# StEth32_Base_XLR_Output.net
KiCad netlist of a schematic drawn in Altium Designer
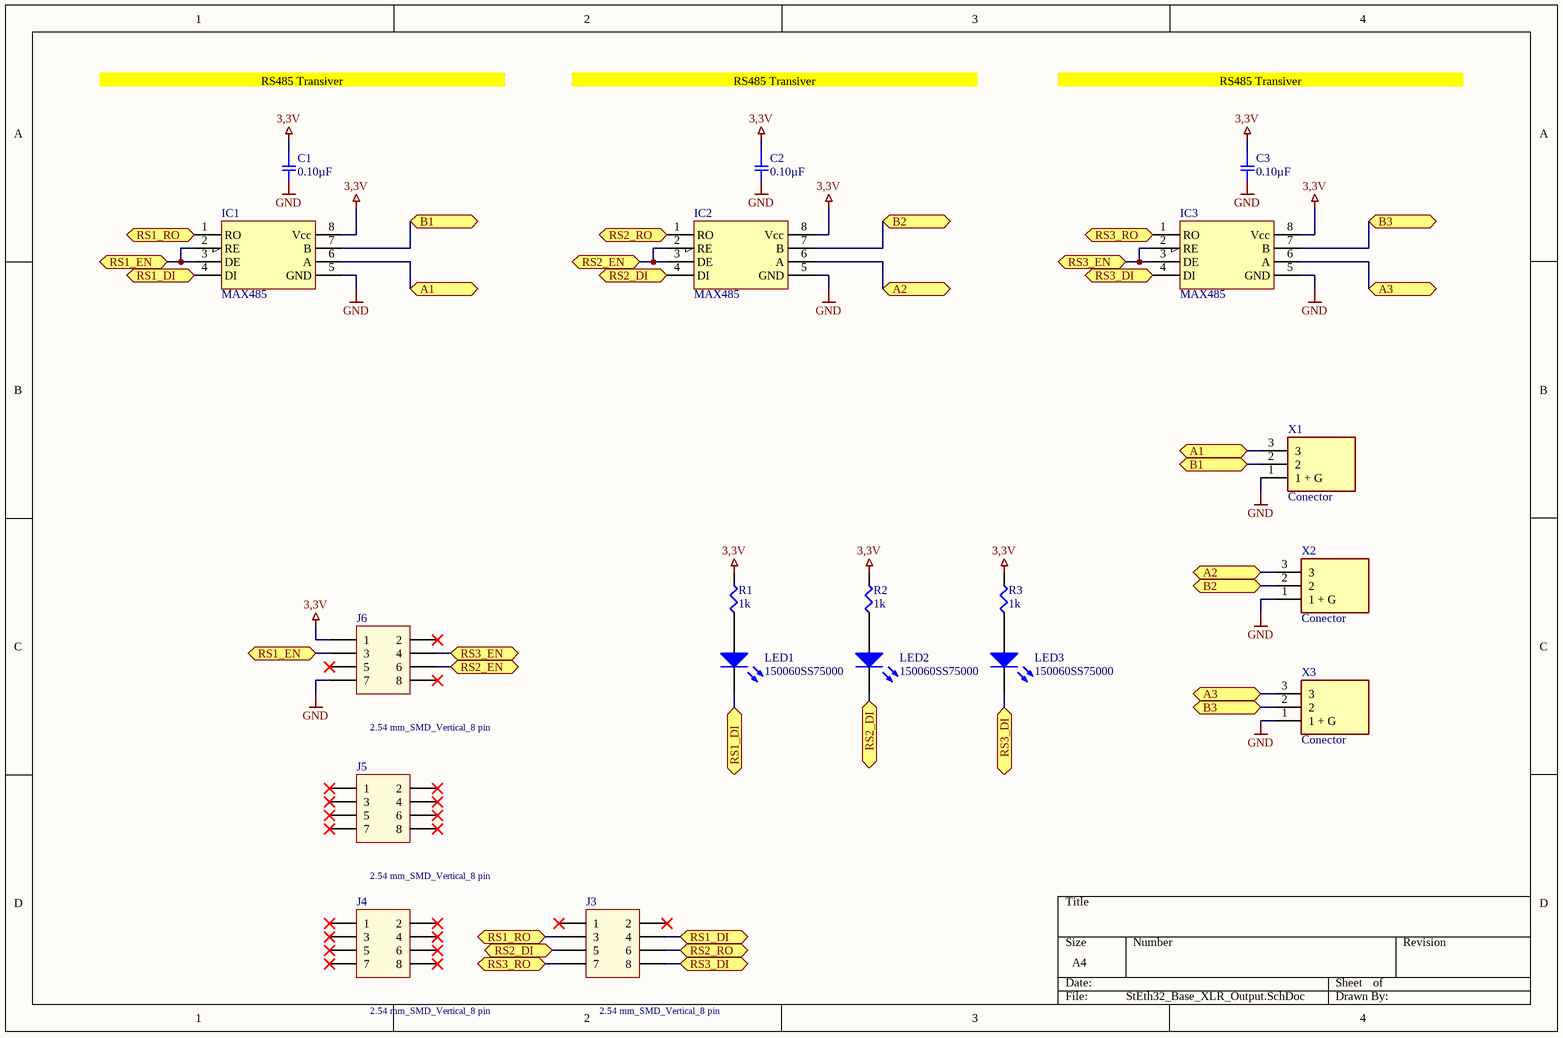
[diagram p0: StEth32_Base_XLR_Output.SchDoc]

(export (version "E")
  (design (tool "Eeschema 10.0.6"))
  (components
    (comp (ref "C1")
      (value "0.10µF")
      (footprint "SMD-0603C")
      (description "CAP CER 0.1UF 16V X7R 0603")
      (fields
        (field (name "DIGI-KEY PART NUMBER") "490-8015-1-ND")
        (field (name "PART NUMBER") "GCM188R71C104KA37J")
      )
      (libsource (lib "capacitor_murata_0603") (part "GCM188R71C104KA37J"))
    )
    (comp (ref "C2")
      (value "0.10µF")
      (footprint "SMD-0603C")
      (description "CAP CER 0.1UF 16V X7R 0603")
      (fields
        (field (name "DIGI-KEY PART NUMBER") "490-8015-1-ND")
        (field (name "PART NUMBER") "GCM188R71C104KA37J")
      )
      (libsource (lib "capacitor_murata_0603") (part "GCM188R71C104KA37J"))
    )
    (comp (ref "C3")
      (value "0.10µF")
      (footprint "SMD-0603C")
      (description "CAP CER 0.1UF 16V X7R 0603")
      (fields
        (field (name "DIGI-KEY PART NUMBER") "490-8015-1-ND")
        (field (name "PART NUMBER") "GCM188R71C104KA37J")
      )
      (libsource (lib "capacitor_murata_0603") (part "GCM188R71C104KA37J"))
    )
    (comp (ref "IC1") (value "MAX485") (footprint "D008_L") (libsource (lib "MyLibs") (part "MAX485")))
    (comp (ref "IC2") (value "MAX485") (footprint "D008_L") (libsource (lib "MyLibs") (part "MAX485")))
    (comp (ref "IC3") (value "MAX485") (footprint "D008_L") (libsource (lib "MyLibs") (part "MAX485")))
    (comp (ref "J3")
      (value "2.54 mm_SMD_Vertical_8 pin")
      (footprint "61030821121")
      (description "Pin Header WR-PHD, pitch 2.54 mm, SMD, Vertical, dual row, 8 pin")
      (fields (field (name "PART NUMBER") "61030821121") (field (name "PUBLISHER") "Wurth Elektronik"))
      (libsource (lib "Altium_WR-PHD_PIN_HEADER_2_54 (rev18a)") (part "61030821121"))
    )
    (comp (ref "J4")
      (value "2.54 mm_SMD_Vertical_8 pin")
      (footprint "61030821121")
      (description "Pin Header WR-PHD, pitch 2.54 mm, SMD, Vertical, dual row, 8 pin")
      (fields (field (name "PART NUMBER") "61030821121") (field (name "PUBLISHER") "Wurth Elektronik"))
      (libsource (lib "Altium_WR-PHD_PIN_HEADER_2_54 (rev18a)") (part "61030821121"))
    )
    (comp (ref "J5")
      (value "2.54 mm_SMD_Vertical_8 pin")
      (footprint "61030821121")
      (description "Pin Header WR-PHD, pitch 2.54 mm, SMD, Vertical, dual row, 8 pin")
      (fields (field (name "PART NUMBER") "61030821121") (field (name "PUBLISHER") "Wurth Elektronik"))
      (libsource (lib "Altium_WR-PHD_PIN_HEADER_2_54 (rev18a)") (part "61030821121"))
    )
    (comp (ref "J6")
      (value "2.54 mm_SMD_Vertical_8 pin")
      (footprint "61030821121")
      (description "Pin Header WR-PHD, pitch 2.54 mm, SMD, Vertical, dual row, 8 pin")
      (fields (field (name "PART NUMBER") "61030821121") (field (name "PUBLISHER") "Wurth Elektronik"))
      (libsource (lib "Altium_WR-PHD_PIN_HEADER_2_54 (rev18a)") (part "61030821121"))
    )
    (comp (ref "LED1")
      (value "150060SS75000")
      (footprint "0603_A")
      (description "SMD mono-color Chip LED, WL-SMCW, Super Red")
      (libsource (lib "WL-SMCW SMD chip LED top view mono-color waterclear") (part "150060SS75000"))
    )
    (comp (ref "LED2")
      (value "150060SS75000")
      (footprint "0603_A")
      (description "SMD mono-color Chip LED, WL-SMCW, Super Red")
      (libsource (lib "WL-SMCW SMD chip LED top view mono-color waterclear") (part "150060SS75000"))
    )
    (comp (ref "LED3")
      (value "150060SS75000")
      (footprint "0603_A")
      (description "SMD mono-color Chip LED, WL-SMCW, Super Red")
      (libsource (lib "WL-SMCW SMD chip LED top view mono-color waterclear") (part "150060SS75000"))
    )
    (comp (ref "R1")
      (value "1k")
      (footprint "SMD-0603-RES")
      (description "RES SMD 1K OHM 1% 1/4W 0603")
      (fields
        (field (name "PART NUMBER") "ERJ-PA3F1001V")
        (field (name "DIGI-KEY PART NUMBER") "P1.0KBYCT-ND")
      )
      (libsource (lib "Panasonic_ERJ_0603") (part "ERJ-PA3F1001V"))
    )
    (comp (ref "R2")
      (value "1k")
      (footprint "SMD-0603-RES")
      (description "RES SMD 1K OHM 1% 1/4W 0603")
      (fields
        (field (name "PART NUMBER") "ERJ-PA3F1001V")
        (field (name "DIGI-KEY PART NUMBER") "P1.0KBYCT-ND")
      )
      (libsource (lib "Panasonic_ERJ_0603") (part "ERJ-PA3F1001V"))
    )
    (comp (ref "R3")
      (value "1k")
      (footprint "SMD-0603-RES")
      (description "RES SMD 1K OHM 1% 1/4W 0603")
      (fields
        (field (name "PART NUMBER") "ERJ-PA3F1001V")
        (field (name "DIGI-KEY PART NUMBER") "P1.0KBYCT-ND")
      )
      (libsource (lib "Panasonic_ERJ_0603") (part "ERJ-PA3F1001V"))
    )
    (comp (ref "X1")
      (value "Conector")
      (footprint "NC3FAAV1")
      (description "Neutrik XLR Connector")
      (libsource (lib "MyLibs") (part "NC3FAAV1"))
    )
    (comp (ref "X2")
      (value "Conector")
      (footprint "NC3FAAV1")
      (description "Neutrik XLR Connector")
      (libsource (lib "MyLibs") (part "NC3FAAV1"))
    )
    (comp (ref "X3")
      (value "Conector")
      (footprint "NC3FAAV1")
      (description "Neutrik XLR Connector")
      (libsource (lib "MyLibs") (part "NC3FAAV1"))
    )
  )
  (nets
    (net (code "1") (name "/A1") (class "Default")
      (node (ref "IC1") (pin "6") (pinfunction "A_6") (pintype "passive"))
      (node (ref "X1") (pin "3") (pinfunction "3_3") (pintype "passive"))
    )
    (net (code "2") (name "/A2") (class "Default")
      (node (ref "IC2") (pin "6") (pinfunction "A_6") (pintype "passive"))
      (node (ref "X2") (pin "3") (pinfunction "3_3") (pintype "passive"))
    )
    (net (code "3") (name "/A3") (class "Default")
      (node (ref "IC3") (pin "6") (pinfunction "A_6") (pintype "passive"))
      (node (ref "X3") (pin "3") (pinfunction "3_3") (pintype "passive"))
    )
    (net (code "4") (name "/B1") (class "Default")
      (node (ref "IC1") (pin "7") (pinfunction "B_7") (pintype "passive"))
      (node (ref "X1") (pin "2") (pinfunction "2_2") (pintype "passive"))
    )
    (net (code "5") (name "/B2") (class "Default")
      (node (ref "IC2") (pin "7") (pinfunction "B_7") (pintype "passive"))
      (node (ref "X2") (pin "2") (pinfunction "2_2") (pintype "passive"))
    )
    (net (code "6") (name "/B3") (class "Default")
      (node (ref "IC3") (pin "7") (pinfunction "B_7") (pintype "passive"))
      (node (ref "X3") (pin "2") (pinfunction "2_2") (pintype "passive"))
    )
    (net (code "7") (name "/RS1_DI") (class "Default")
      (node (ref "IC1") (pin "4") (pinfunction "DI_4") (pintype "passive"))
      (node (ref "J3") (pin "4") (pinfunction "4_4") (pintype "passive"))
      (node (ref "LED1") (pin "1") (pinfunction "K_1") (pintype "passive"))
    )
    (net (code "8") (name "/RS1_EN") (class "Default")
      (node (ref "IC1") (pin "2") (pinfunction "RE_2") (pintype "passive"))
      (node (ref "IC1") (pin "3") (pinfunction "DE_3") (pintype "passive"))
      (node (ref "J6") (pin "3") (pinfunction "3_3") (pintype "passive"))
    )
    (net (code "9") (name "/RS1_RO") (class "Default")
      (node (ref "IC1") (pin "1") (pinfunction "RO_1") (pintype "passive"))
      (node (ref "J3") (pin "3") (pinfunction "3_3") (pintype "passive"))
    )
    (net (code "10") (name "/RS2_DI") (class "Default")
      (node (ref "IC2") (pin "4") (pinfunction "DI_4") (pintype "passive"))
      (node (ref "J3") (pin "5") (pinfunction "5_5") (pintype "passive"))
      (node (ref "LED2") (pin "1") (pinfunction "K_1") (pintype "passive"))
    )
    (net (code "11") (name "/RS2_EN") (class "Default")
      (node (ref "IC2") (pin "2") (pinfunction "RE_2") (pintype "passive"))
      (node (ref "IC2") (pin "3") (pinfunction "DE_3") (pintype "passive"))
      (node (ref "J6") (pin "6") (pinfunction "6_6") (pintype "passive"))
    )
    (net (code "12") (name "/RS2_RO") (class "Default")
      (node (ref "IC2") (pin "1") (pinfunction "RO_1") (pintype "passive"))
      (node (ref "J3") (pin "6") (pinfunction "6_6") (pintype "passive"))
    )
    (net (code "13") (name "/RS3_DI") (class "Default")
      (node (ref "IC3") (pin "4") (pinfunction "DI_4") (pintype "passive"))
      (node (ref "J3") (pin "8") (pinfunction "8_8") (pintype "passive"))
      (node (ref "LED3") (pin "1") (pinfunction "K_1") (pintype "passive"))
    )
    (net (code "14") (name "/RS3_EN") (class "Default")
      (node (ref "IC3") (pin "2") (pinfunction "RE_2") (pintype "passive"))
      (node (ref "IC3") (pin "3") (pinfunction "DE_3") (pintype "passive"))
      (node (ref "J6") (pin "4") (pinfunction "4_4") (pintype "passive"))
    )
    (net (code "15") (name "/RS3_RO") (class "Default")
      (node (ref "IC3") (pin "1") (pinfunction "RO_1") (pintype "passive"))
      (node (ref "J3") (pin "7") (pinfunction "7_7") (pintype "passive"))
    )
    (net (code "16") (name "3,3V") (class "Default")
      (node (ref "C1") (pin "1") (pinfunction "1_1") (pintype "passive"))
      (node (ref "C2") (pin "1") (pinfunction "1_1") (pintype "passive"))
      (node (ref "C3") (pin "1") (pinfunction "1_1") (pintype "passive"))
      (node (ref "IC1") (pin "8") (pinfunction "Vcc_8") (pintype "passive"))
      (node (ref "IC2") (pin "8") (pinfunction "Vcc_8") (pintype "passive"))
      (node (ref "IC3") (pin "8") (pinfunction "Vcc_8") (pintype "passive"))
      (node (ref "J6") (pin "1") (pinfunction "1_1") (pintype "passive"))
      (node (ref "R1") (pin "2") (pinfunction "2_2") (pintype "passive"))
      (node (ref "R2") (pin "2") (pinfunction "2_2") (pintype "passive"))
      (node (ref "R3") (pin "2") (pinfunction "2_2") (pintype "passive"))
    )
    (net (code "17") (name "GND") (class "Default")
      (node (ref "C1") (pin "2") (pinfunction "2_2") (pintype "passive"))
      (node (ref "C2") (pin "2") (pinfunction "2_2") (pintype "passive"))
      (node (ref "C3") (pin "2") (pinfunction "2_2") (pintype "passive"))
      (node (ref "IC1") (pin "5") (pinfunction "GND_5") (pintype "passive"))
      (node (ref "IC2") (pin "5") (pinfunction "GND_5") (pintype "passive"))
      (node (ref "IC3") (pin "5") (pinfunction "GND_5") (pintype "passive"))
      (node (ref "J6") (pin "7") (pinfunction "7_7") (pintype "passive"))
      (node (ref "X1") (pin "1") (pinfunction "1_+_G_1") (pintype "passive"))
      (node (ref "X2") (pin "1") (pinfunction "1_+_G_1") (pintype "passive"))
      (node (ref "X3") (pin "1") (pinfunction "1_+_G_1") (pintype "passive"))
    )
    (net (code "18") (name "Net-(LED1-A)") (class "Default")
      (node (ref "LED1") (pin "2") (pinfunction "A_2") (pintype "passive"))
      (node (ref "R1") (pin "1") (pinfunction "1_1") (pintype "passive"))
    )
    (net (code "19") (name "Net-(LED2-A)") (class "Default")
      (node (ref "LED2") (pin "2") (pinfunction "A_2") (pintype "passive"))
      (node (ref "R2") (pin "1") (pinfunction "1_1") (pintype "passive"))
    )
    (net (code "20") (name "Net-(LED3-A)") (class "Default")
      (node (ref "LED3") (pin "2") (pinfunction "A_2") (pintype "passive"))
      (node (ref "R3") (pin "1") (pinfunction "1_1") (pintype "passive"))
    )
    (net (code "21") (name "unconnected-(J3-Pad1)") (class "Default")
      (node (ref "J3") (pin "1") (pinfunction "1_1") (pintype "passive+no_connect"))
    )
    (net (code "22") (name "unconnected-(J3-Pad2)") (class "Default")
      (node (ref "J3") (pin "2") (pinfunction "2_2") (pintype "passive+no_connect"))
    )
    (net (code "23") (name "unconnected-(J4-Pad1)") (class "Default")
      (node (ref "J4") (pin "1") (pinfunction "1_1") (pintype "passive+no_connect"))
    )
    (net (code "24") (name "unconnected-(J4-Pad2)") (class "Default")
      (node (ref "J4") (pin "2") (pinfunction "2_2") (pintype "passive+no_connect"))
    )
    (net (code "25") (name "unconnected-(J4-Pad3)") (class "Default")
      (node (ref "J4") (pin "3") (pinfunction "3_3") (pintype "passive+no_connect"))
    )
    (net (code "26") (name "unconnected-(J4-Pad4)") (class "Default")
      (node (ref "J4") (pin "4") (pinfunction "4_4") (pintype "passive+no_connect"))
    )
    (net (code "27") (name "unconnected-(J4-Pad5)") (class "Default")
      (node (ref "J4") (pin "5") (pinfunction "5_5") (pintype "passive+no_connect"))
    )
    (net (code "28") (name "unconnected-(J4-Pad6)") (class "Default")
      (node (ref "J4") (pin "6") (pinfunction "6_6") (pintype "passive+no_connect"))
    )
    (net (code "29") (name "unconnected-(J4-Pad7)") (class "Default")
      (node (ref "J4") (pin "7") (pinfunction "7_7") (pintype "passive+no_connect"))
    )
    (net (code "30") (name "unconnected-(J4-Pad8)") (class "Default")
      (node (ref "J4") (pin "8") (pinfunction "8_8") (pintype "passive+no_connect"))
    )
    (net (code "31") (name "unconnected-(J5-Pad1)") (class "Default")
      (node (ref "J5") (pin "1") (pinfunction "1_1") (pintype "passive+no_connect"))
    )
    (net (code "32") (name "unconnected-(J5-Pad2)") (class "Default")
      (node (ref "J5") (pin "2") (pinfunction "2_2") (pintype "passive+no_connect"))
    )
    (net (code "33") (name "unconnected-(J5-Pad3)") (class "Default")
      (node (ref "J5") (pin "3") (pinfunction "3_3") (pintype "passive+no_connect"))
    )
    (net (code "34") (name "unconnected-(J5-Pad4)") (class "Default")
      (node (ref "J5") (pin "4") (pinfunction "4_4") (pintype "passive+no_connect"))
    )
    (net (code "35") (name "unconnected-(J5-Pad5)") (class "Default")
      (node (ref "J5") (pin "5") (pinfunction "5_5") (pintype "passive+no_connect"))
    )
    (net (code "36") (name "unconnected-(J5-Pad6)") (class "Default")
      (node (ref "J5") (pin "6") (pinfunction "6_6") (pintype "passive+no_connect"))
    )
    (net (code "37") (name "unconnected-(J5-Pad7)") (class "Default")
      (node (ref "J5") (pin "7") (pinfunction "7_7") (pintype "passive+no_connect"))
    )
    (net (code "38") (name "unconnected-(J5-Pad8)") (class "Default")
      (node (ref "J5") (pin "8") (pinfunction "8_8") (pintype "passive+no_connect"))
    )
    (net (code "39") (name "unconnected-(J6-Pad2)") (class "Default")
      (node (ref "J6") (pin "2") (pinfunction "2_2") (pintype "passive+no_connect"))
    )
    (net (code "40") (name "unconnected-(J6-Pad5)") (class "Default")
      (node (ref "J6") (pin "5") (pinfunction "5_5") (pintype "passive+no_connect"))
    )
    (net (code "41") (name "unconnected-(J6-Pad8)") (class "Default")
      (node (ref "J6") (pin "8") (pinfunction "8_8") (pintype "passive+no_connect"))
    )
  )
)
